# SensorInterface.net
KiCad netlist of a schematic drawn in EAGLE
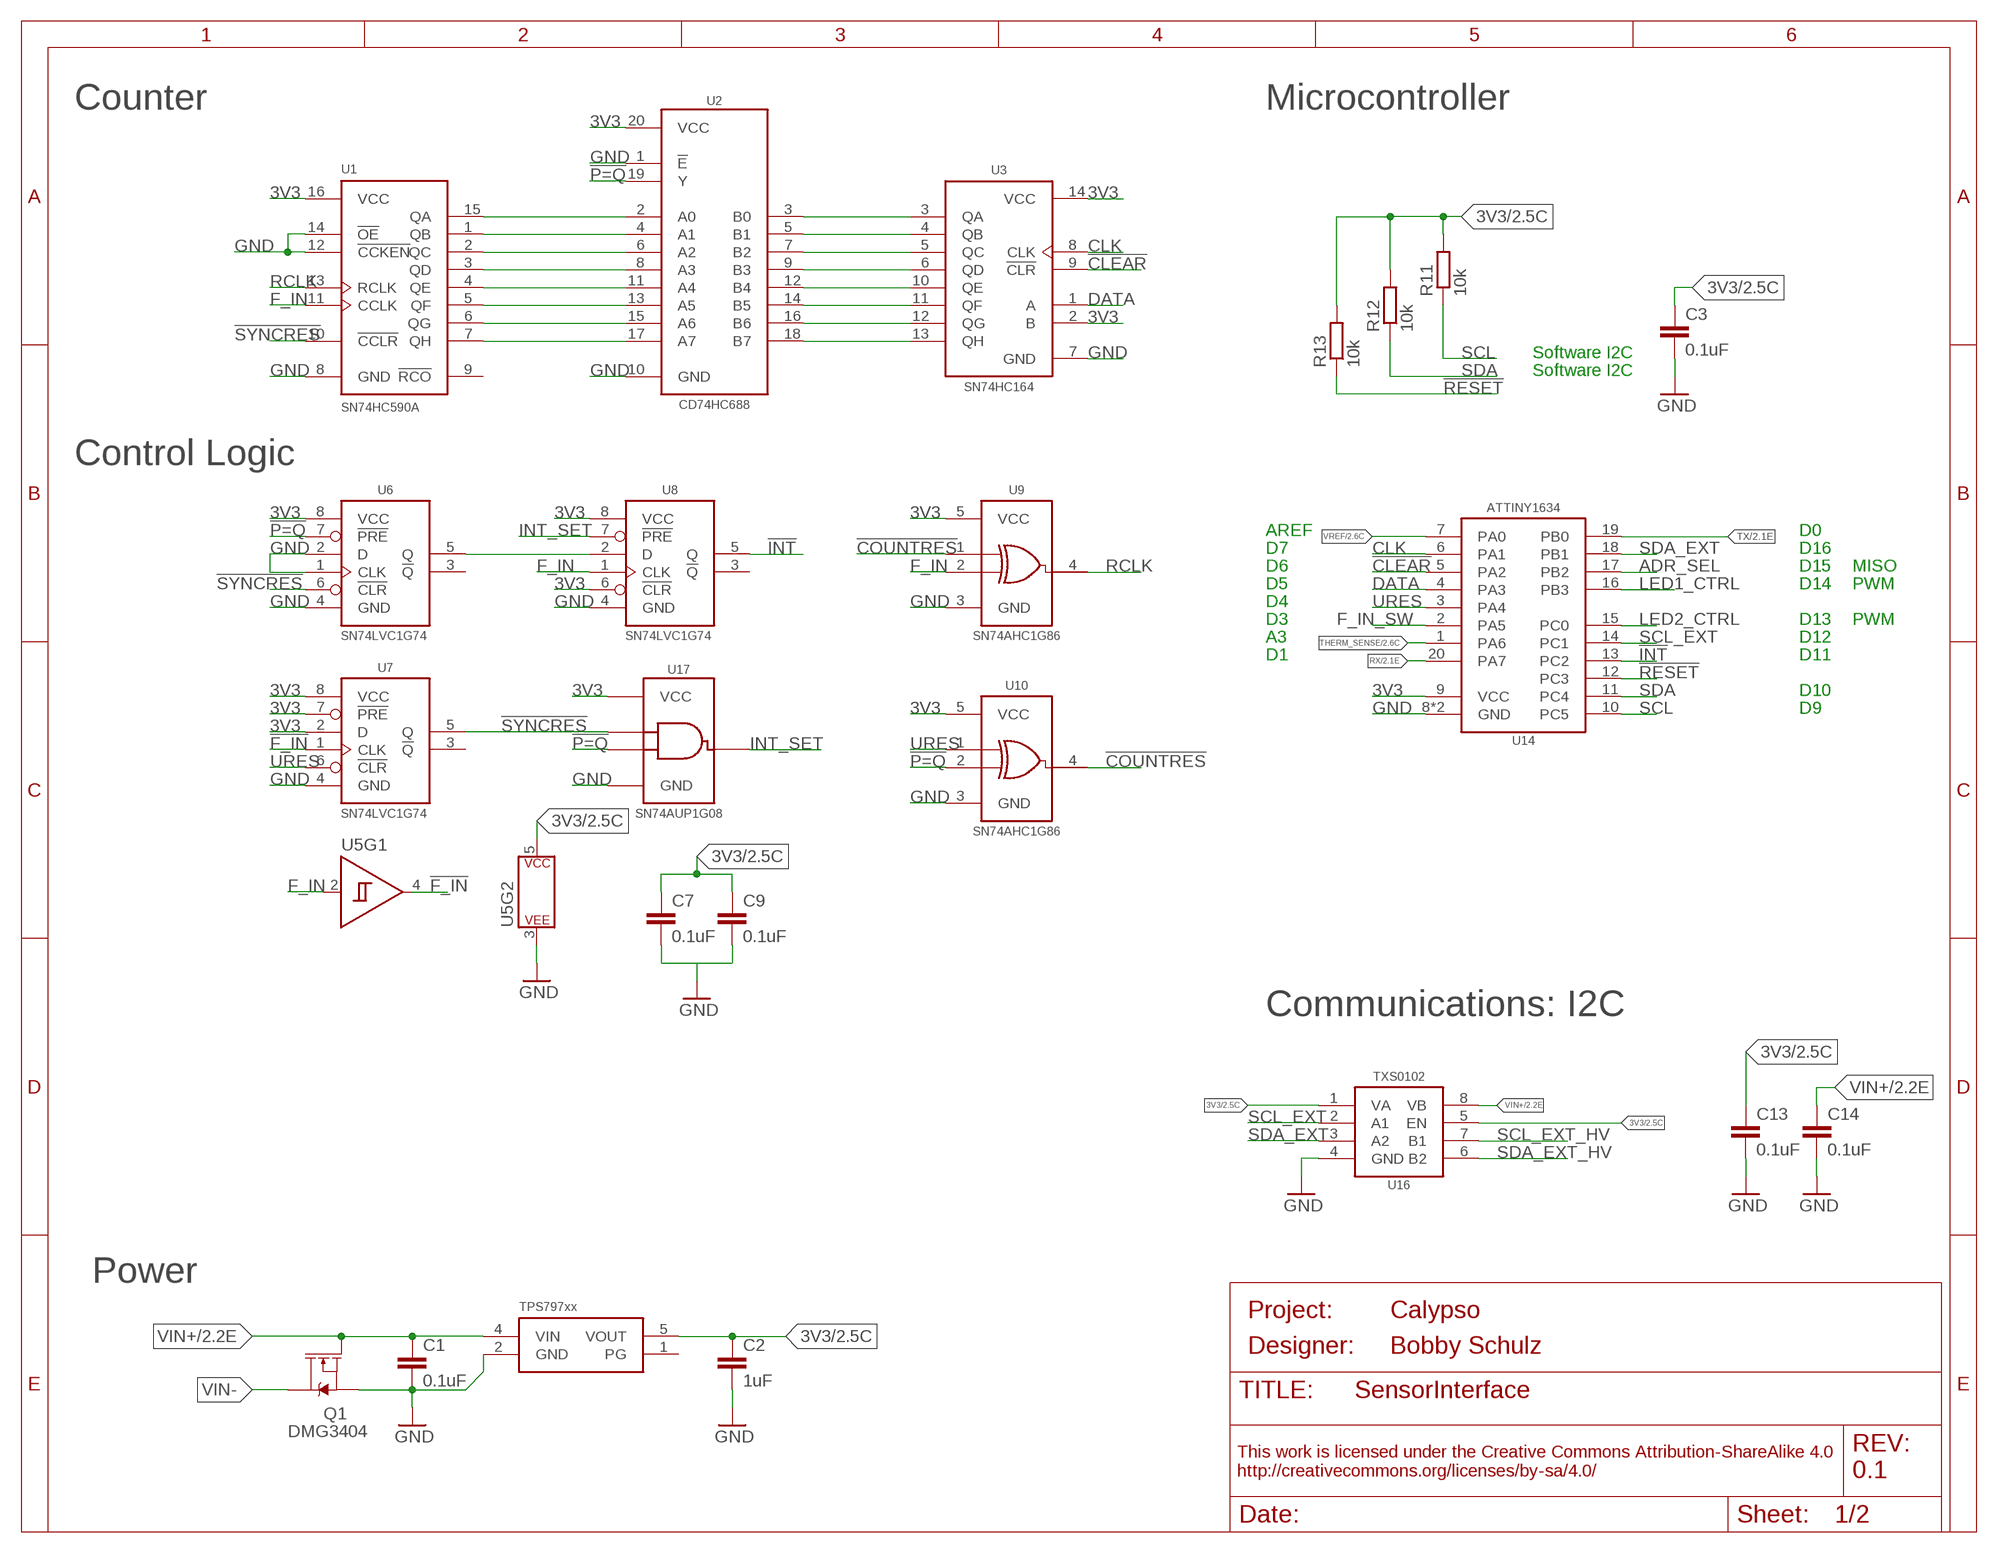
[diagram p0: schematic, sheet 1]
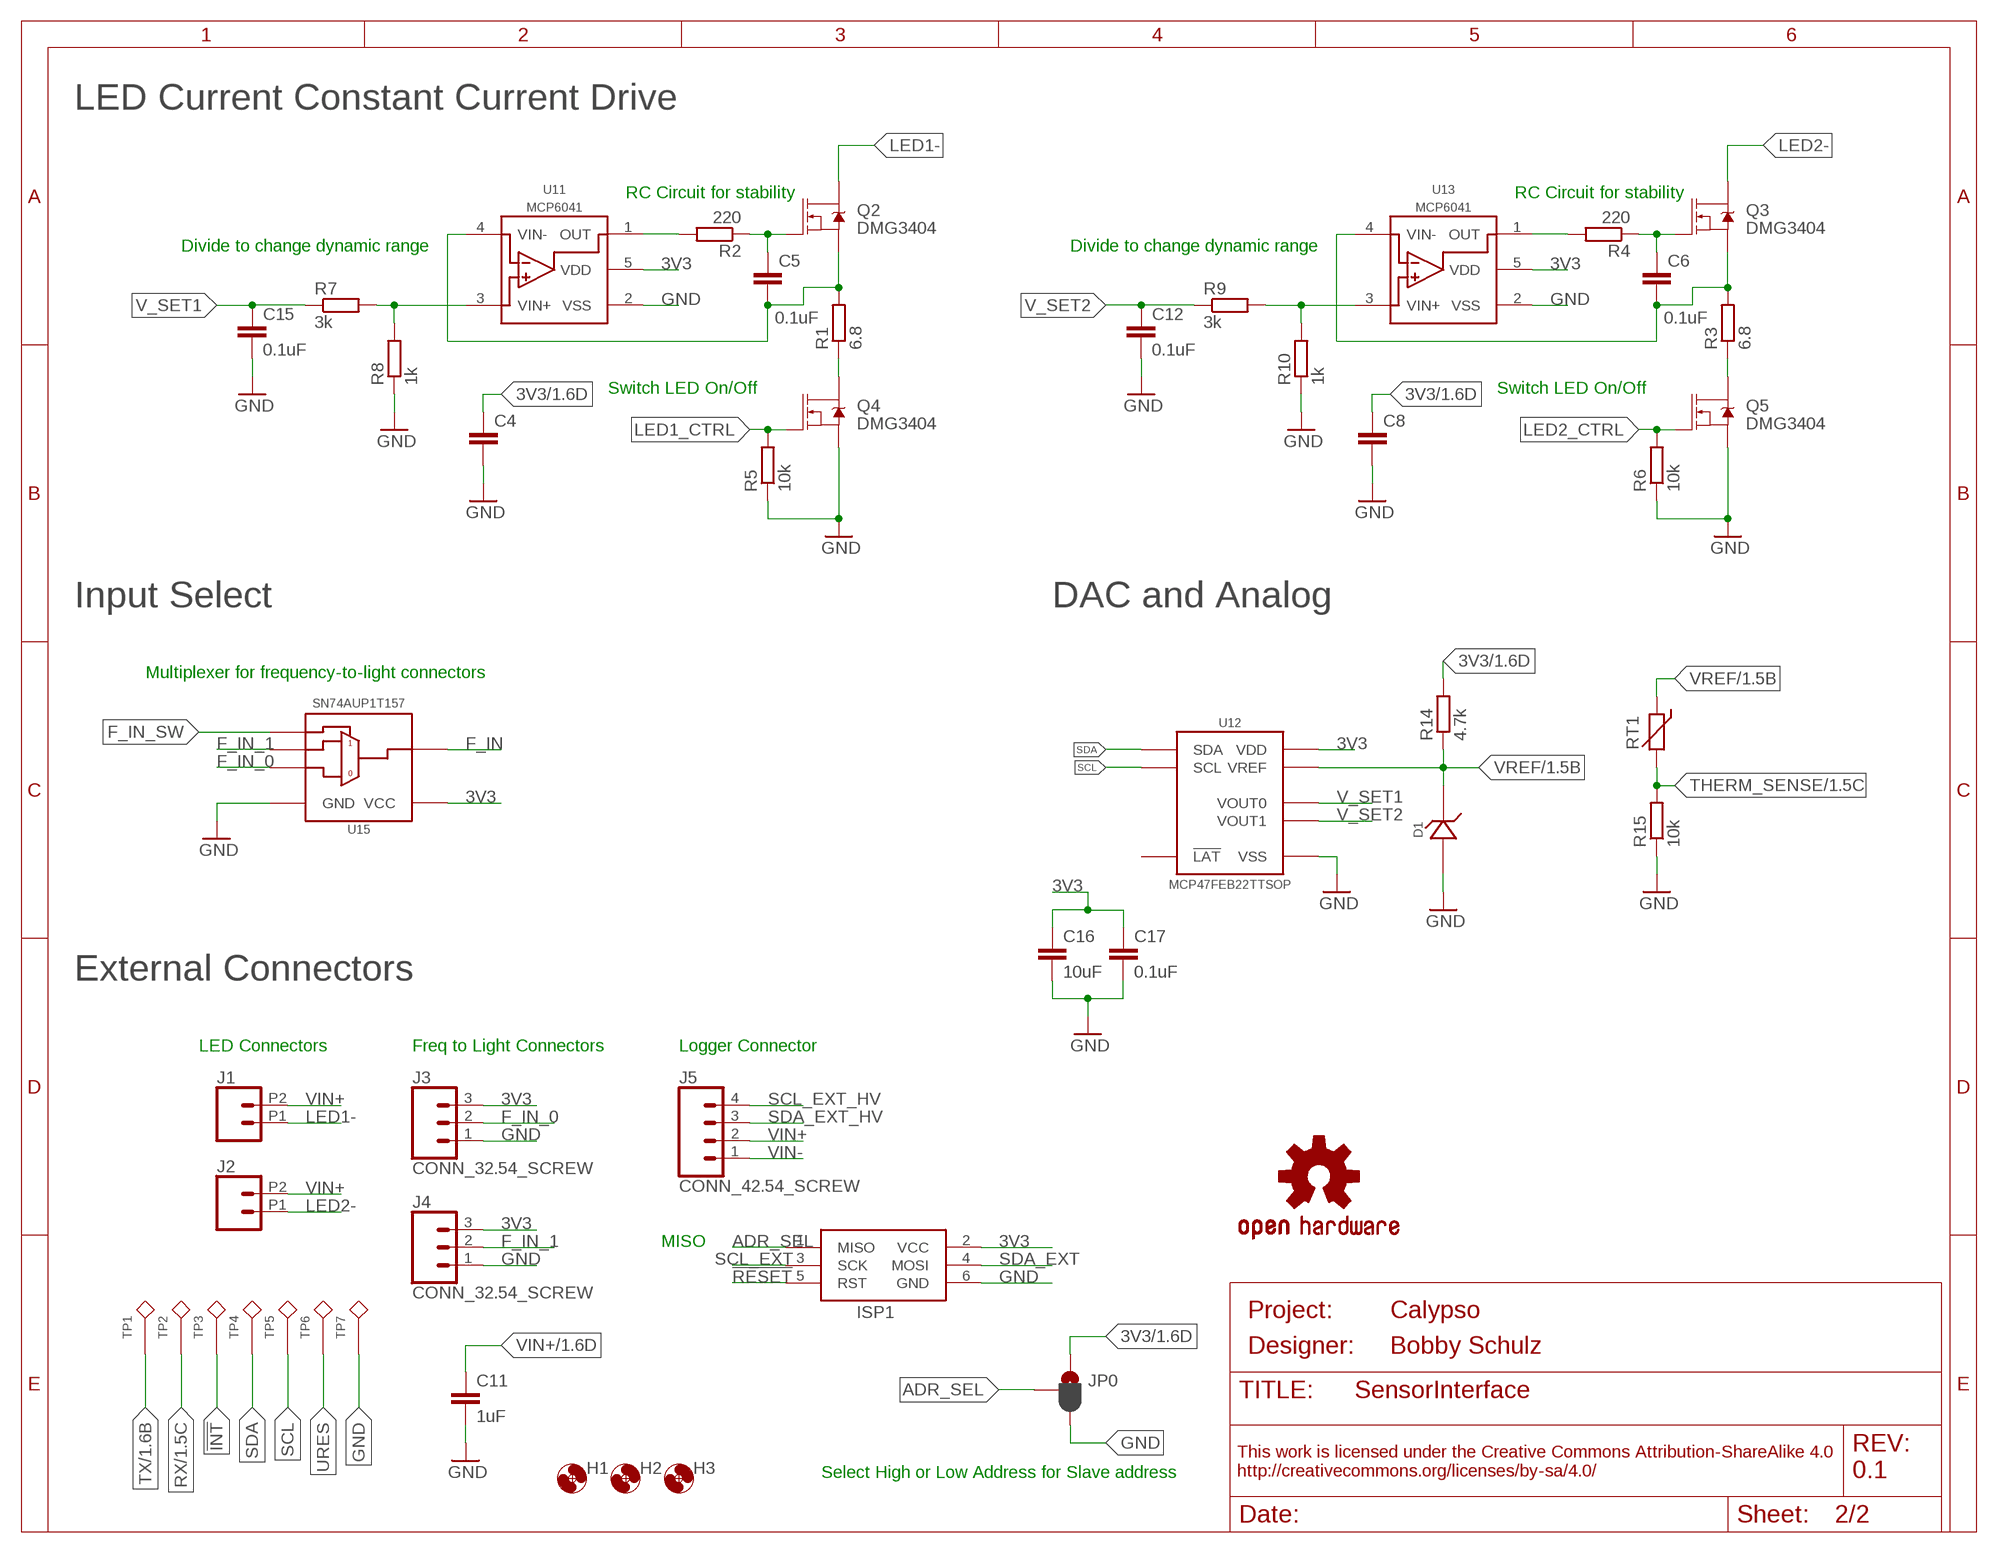
[diagram p1: schematic, sheet 2]

(export (version "E")
  (design (tool "Eeschema 10.0.6"))
  (components
    (comp (ref "C4")
      (value "C-EU0.1UFC0402")
      (footprint "eagle-import:C0402")
      (fields (field (name "MF") "Murata") (field (name "MPN") "GCM155R71C104KA55D"))
      (libsource (lib "eagle-import") (part "C-EUC04020.1UF"))
    )
    (comp (ref "C5")
      (value "0.1uF")
      (footprint "eagle-import:C0603")
      (libsource (lib "eagle-import") (part "C-EUC0603"))
    )
    (comp (ref "C6")
      (value "0.1uF")
      (footprint "eagle-import:C0603")
      (libsource (lib "eagle-import") (part "C-EUC0603"))
    )
    (comp (ref "C8")
      (value "C-EU0.1UFC0402")
      (footprint "eagle-import:C0402")
      (fields (field (name "MF") "Murata") (field (name "MPN") "GCM155R71C104KA55D"))
      (libsource (lib "eagle-import") (part "C-EUC04020.1UF"))
    )
    (comp (ref "C11")
      (value "1uF")
      (footprint "eagle-import:C0603")
      (libsource (lib "eagle-import") (part "C-EUC0603"))
    )
    (comp (ref "C12")
      (value "0.1uF")
      (footprint "eagle-import:C0603")
      (fields (field (name "MF") "Murata") (field (name "MPN") "GCM188R71E104KA57D"))
      (libsource (lib "eagle-import") (part "C-EUC06030.1UF"))
    )
    (comp (ref "C15")
      (value "0.1uF")
      (footprint "eagle-import:C0603")
      (fields (field (name "MF") "Murata") (field (name "MPN") "GCM188R71E104KA57D"))
      (libsource (lib "eagle-import") (part "C-EUC06030.1UF"))
    )
    (comp (ref "C16")
      (value "10uF")
      (footprint "eagle-import:C0805")
      (libsource (lib "eagle-import") (part "C-EUC0805"))
    )
    (comp (ref "C17")
      (value "0.1uF")
      (footprint "eagle-import:C0603")
      (libsource (lib "eagle-import") (part "C-EUC0603"))
    )
    (comp (ref "D1")
      (value "LM40402.048")
      (footprint "eagle-import:SOT23-3")
      (fields (field (name "MF") "TI") (field (name "MPN") "LM4040CIM3-2.0/NOPB"))
      (libsource (lib "eagle-import") (part "LM40402.048"))
    )
    (comp (ref "H1")
      (value "MOUNTING_HOLE2_NP")
      (footprint "eagle-import:2_56")
      (libsource (lib "eagle-import") (part "MOUNTING_HOLE2_NP"))
    )
    (comp (ref "H2")
      (value "MOUNTING_HOLE2_NP")
      (footprint "eagle-import:2_56")
      (libsource (lib "eagle-import") (part "MOUNTING_HOLE2_NP"))
    )
    (comp (ref "H3")
      (value "MOUNTING_HOLE2_NP")
      (footprint "eagle-import:2_56")
      (libsource (lib "eagle-import") (part "MOUNTING_HOLE2_NP"))
    )
    (comp (ref "ISP1")
      (value "AVRISP-6")
      (footprint "eagle-import:AVRISP")
      (libsource (lib "eagle-import") (part "AVRISP-6"))
    )
    (comp (ref "J1")
      (value "CONN_02SCREW_2.54")
      (footprint "eagle-import:1X02_2.54_SCREWTERM")
      (fields (field (name "MF") "OnShore") (field (name "MPN") "OSTVN02A150"))
      (libsource (lib "eagle-import") (part "CONN_02SCREW_2.54"))
    )
    (comp (ref "J2")
      (value "CONN_02SCREW_2.54")
      (footprint "eagle-import:1X02_2.54_SCREWTERM")
      (fields (field (name "MF") "OnShore") (field (name "MPN") "OSTVN02A150"))
      (libsource (lib "eagle-import") (part "CONN_02SCREW_2.54"))
    )
    (comp (ref "J3")
      (value "CONN_32.54_SCREW")
      (footprint "eagle-import:1X03_SCREW")
      (libsource (lib "eagle-import") (part "CONN_32.54_SCREW"))
    )
    (comp (ref "J4")
      (value "CONN_32.54_SCREW")
      (footprint "eagle-import:1X03_SCREW")
      (libsource (lib "eagle-import") (part "CONN_32.54_SCREW"))
    )
    (comp (ref "J5")
      (value "CONN_42.54_SCREW")
      (footprint "eagle-import:1X04_SCREW")
      (fields (field (name "MF") "On Shore") (field (name "MPN") "OSTVN04A150"))
      (libsource (lib "eagle-import") (part "CONN_42.54_SCREW"))
    )
    (comp (ref "JP0")
      (value "JUMPER-SMT_3_1-NC_PASTE_SILK")
      (footprint "eagle-import:SMT-JUMPER_3_1-NC_PASTE_SILK")
      (libsource (lib "eagle-import") (part "JUMPER-SMT_3_1-NC_PASTE_SILK"))
    )
    (comp (ref "LOGO1")
      (value "OSHW-LOGOM")
      (footprint "eagle-import:OSHW-LOGO-M")
      (libsource (lib "eagle-import") (part "OSHW-LOGOM"))
    )
    (comp (ref "Q2")
      (value "DMG3404")
      (footprint "eagle-import:SOT23-3")
      (fields (field (name "MF") "Diodes Incorporated") (field (name "MPN") "DMG3404L-7"))
      (libsource (lib "eagle-import") (part "MOSFET-NCH-DMG3404L"))
    )
    (comp (ref "Q3")
      (value "DMG3404")
      (footprint "eagle-import:SOT23-3")
      (fields (field (name "MF") "Diodes Incorporated") (field (name "MPN") "DMG3404L-7"))
      (libsource (lib "eagle-import") (part "MOSFET-NCH-DMG3404L"))
    )
    (comp (ref "Q4")
      (value "DMG3404")
      (footprint "eagle-import:SOT23-3")
      (fields (field (name "MF") "Diodes Incorporated") (field (name "MPN") "DMG3404L-7"))
      (libsource (lib "eagle-import") (part "MOSFET-NCH-DMG3404L"))
    )
    (comp (ref "Q5")
      (value "DMG3404")
      (footprint "eagle-import:SOT23-3")
      (fields (field (name "MF") "Diodes Incorporated") (field (name "MPN") "DMG3404L-7"))
      (libsource (lib "eagle-import") (part "MOSFET-NCH-DMG3404L"))
    )
    (comp (ref "R1")
      (value "6.8")
      (footprint "eagle-import:R0603")
      (fields (field (name "MF") "Yageo"))
      (libsource (lib "eagle-import") (part "R-EU_R0603"))
    )
    (comp (ref "R2")
      (value "220")
      (footprint "eagle-import:R0603")
      (fields (field (name "MF") "Yageo"))
      (libsource (lib "eagle-import") (part "R-EU_R0603"))
    )
    (comp (ref "R3")
      (value "6.8")
      (footprint "eagle-import:R0603")
      (fields (field (name "MF") "Yageo"))
      (libsource (lib "eagle-import") (part "R-EU_R0603"))
    )
    (comp (ref "R4")
      (value "220")
      (footprint "eagle-import:R0603")
      (fields (field (name "MF") "Yageo"))
      (libsource (lib "eagle-import") (part "R-EU_R0603"))
    )
    (comp (ref "R5")
      (value "10k")
      (footprint "eagle-import:R0603")
      (fields (field (name "MF") "Yageo"))
      (libsource (lib "eagle-import") (part "R-EU_R0603"))
    )
    (comp (ref "R6")
      (value "10k")
      (footprint "eagle-import:R0603")
      (fields (field (name "MF") "Yageo"))
      (libsource (lib "eagle-import") (part "R-EU_R0603"))
    )
    (comp (ref "R7")
      (value "3k")
      (footprint "eagle-import:R0603")
      (fields (field (name "MF") "Yageo"))
      (libsource (lib "eagle-import") (part "R-EU_R0603"))
    )
    (comp (ref "R8")
      (value "1k")
      (footprint "eagle-import:R0603")
      (fields (field (name "MF") "Yageo"))
      (libsource (lib "eagle-import") (part "R-EU_R0603"))
    )
    (comp (ref "R9")
      (value "3k")
      (footprint "eagle-import:R0603")
      (fields (field (name "MF") "Yageo"))
      (libsource (lib "eagle-import") (part "R-EU_R0603"))
    )
    (comp (ref "R10")
      (value "1k")
      (footprint "eagle-import:R0603")
      (fields (field (name "MF") "Yageo"))
      (libsource (lib "eagle-import") (part "R-EU_R0603"))
    )
    (comp (ref "R14")
      (value "4.7k")
      (footprint "eagle-import:R0603")
      (fields (field (name "MF") "Yageo"))
      (libsource (lib "eagle-import") (part "R-EU_R0603"))
    )
    (comp (ref "R15")
      (value "10k")
      (footprint "eagle-import:R0603")
      (fields (field (name "MF") "Panasonic") (field (name "MPN") "ERA-3AEB103V"))
      (libsource (lib "eagle-import") (part "R-EU_R0603P10K"))
    )
    (comp (ref "RT1")
      (value "THERMISTOR10K")
      (footprint "eagle-import:R0603")
      (fields (field (name "MF") "Murata") (field (name "MPN") "NCU18XH103F60RB"))
      (libsource (lib "eagle-import") (part "THERMISTOR10K"))
    )
    (comp (ref "TP1")
      (value "TESTPOINTRCU")
      (footprint "eagle-import:TESTPOINT_0603")
      (fields (field (name "MF") "TE Connectivity") (field (name "MPN") "RCU-0C"))
      (libsource (lib "eagle-import") (part "TESTPOINTRCU"))
    )
    (comp (ref "TP2")
      (value "TESTPOINTRCU")
      (footprint "eagle-import:TESTPOINT_0603")
      (fields (field (name "MF") "TE Connectivity") (field (name "MPN") "RCU-0C"))
      (libsource (lib "eagle-import") (part "TESTPOINTRCU"))
    )
    (comp (ref "TP3")
      (value "TESTPOINTRCU")
      (footprint "eagle-import:TESTPOINT_0603")
      (fields (field (name "MF") "TE Connectivity") (field (name "MPN") "RCU-0C"))
      (libsource (lib "eagle-import") (part "TESTPOINTRCU"))
    )
    (comp (ref "TP4")
      (value "TESTPOINTRCU")
      (footprint "eagle-import:TESTPOINT_0603")
      (fields (field (name "MF") "TE Connectivity") (field (name "MPN") "RCU-0C"))
      (libsource (lib "eagle-import") (part "TESTPOINTRCU"))
    )
    (comp (ref "TP5")
      (value "TESTPOINTRCU")
      (footprint "eagle-import:TESTPOINT_0603")
      (fields (field (name "MF") "TE Connectivity") (field (name "MPN") "RCU-0C"))
      (libsource (lib "eagle-import") (part "TESTPOINTRCU"))
    )
    (comp (ref "TP6")
      (value "TESTPOINTRCU")
      (footprint "eagle-import:TESTPOINT_0603")
      (fields (field (name "MF") "TE Connectivity") (field (name "MPN") "RCU-0C"))
      (libsource (lib "eagle-import") (part "TESTPOINTRCU"))
    )
    (comp (ref "TP7")
      (value "TESTPOINTRCU")
      (footprint "eagle-import:TESTPOINT_0603")
      (fields (field (name "MF") "TE Connectivity") (field (name "MPN") "RCU-0C"))
      (libsource (lib "eagle-import") (part "TESTPOINTRCU"))
    )
    (comp (ref "U11")
      (value "MCP6041")
      (footprint "eagle-import:SOT23-5")
      (fields
        (field (name "DISP") "MCP6041")
        (field (name "MF") "Microchip")
        (field (name "MPN") "MCP6041T-I/OT")
      )
      (libsource (lib "eagle-import") (part "MCP6041"))
    )
    (comp (ref "U12")
      (value "MCP47FEB22TTSOP")
      (footprint "eagle-import:TTSOP_8")
      (fields (field (name "MF") "Microchip") (field (name "MPN") "MCP47FEB22A0-E/ST"))
      (libsource (lib "eagle-import") (part "MCP47FEB2TTSOP2"))
    )
    (comp (ref "U13")
      (value "MCP6041")
      (footprint "eagle-import:SOT23-5")
      (fields
        (field (name "DISP") "MCP6041")
        (field (name "MF") "Microchip")
        (field (name "MPN") "MCP6041T-I/OT")
      )
      (libsource (lib "eagle-import") (part "MCP6041"))
    )
    (comp (ref "U15")
      (value "SN74AUP1T157DCK")
      (footprint "eagle-import:DCK_R-PDSO-G6")
      (fields
        (field (name "DISP") "SN74AUP1T157")
        (field (name "MF") "TI")
        (field (name "MPN") "SN74AUP1T157DCKR")
      )
      (libsource (lib "eagle-import") (part "SN74AUP1T157DCK"))
    )
    (comp (ref "C1")
      (value "0.1uF")
      (footprint "eagle-import:C0603")
      (fields (field (name "MF") "Murata") (field (name "MPN") "GCM188R71E104KA57D"))
      (libsource (lib "eagle-import") (part "C-EUC06030.1UF"))
    )
    (comp (ref "C2")
      (value "1uF")
      (footprint "eagle-import:C0603")
      (fields (field (name "MF") "Murata") (field (name "MPN") "GRM188R61C105KA12D"))
      (libsource (lib "eagle-import") (part "C-EUC06031UF"))
    )
    (comp (ref "C3")
      (value "0.1uF")
      (footprint "eagle-import:C0402")
      (fields (field (name "MF") "Murata") (field (name "MPN") "GCM155R71C104KA55D"))
      (libsource (lib "eagle-import") (part "C-EUC04020.1UF"))
    )
    (comp (ref "C7")
      (value "0.1uF")
      (footprint "eagle-import:C0603")
      (libsource (lib "eagle-import") (part "C-EUC0603"))
    )
    (comp (ref "C9")
      (value "0.1uF")
      (footprint "eagle-import:C0603")
      (libsource (lib "eagle-import") (part "C-EUC0603"))
    )
    (comp (ref "C13")
      (value "0.1uF")
      (footprint "eagle-import:C0402")
      (fields (field (name "MF") "Murata") (field (name "MPN") "GCM155R71C104KA55D"))
      (libsource (lib "eagle-import") (part "C-EUC04020.1UF"))
    )
    (comp (ref "C14")
      (value "0.1uF")
      (footprint "eagle-import:C0402")
      (fields (field (name "MF") "Murata") (field (name "MPN") "GCM155R71C104KA55D"))
      (libsource (lib "eagle-import") (part "C-EUC04020.1UF"))
    )
    (comp (ref "Q1")
      (value "DMG3404")
      (footprint "eagle-import:SOT23-3")
      (fields (field (name "MF") "Diodes Incorporated") (field (name "MPN") "DMG3404L-7"))
      (libsource (lib "eagle-import") (part "MOSFET-NCH-DMG3404L"))
    )
    (comp (ref "R11")
      (value "10k")
      (footprint "eagle-import:R0402")
      (fields (field (name "MF") "Yageo") (field (name "MPN") "RC0402JR-0710KL"))
      (libsource (lib "eagle-import") (part "R-EU_R040210K"))
    )
    (comp (ref "R12")
      (value "10k")
      (footprint "eagle-import:R0402")
      (fields (field (name "MF") "Yageo") (field (name "MPN") "RC0402JR-0710KL"))
      (libsource (lib "eagle-import") (part "R-EU_R040210K"))
    )
    (comp (ref "R13")
      (value "10k")
      (footprint "eagle-import:R0402")
      (fields (field (name "MF") "Yageo") (field (name "MPN") "RC0402JR-0710KL"))
      (libsource (lib "eagle-import") (part "R-EU_R040210K"))
    )
    (comp (ref "U$1")
      (value "TPS79733")
      (footprint "eagle-import:DCK_R-PDSO-G5")
      (fields (field (name "MF") "TI") (field (name "MPN") "TPS79733DCKR"))
      (libsource (lib "eagle-import") (part "TPS79733"))
    )
    (comp (ref "U1")
      (value "SN74HC590AD")
      (footprint "eagle-import:SO16")
      (fields (field (name "MF") "TI"))
      (libsource (lib "eagle-import") (part "SN74HC590AD"))
    )
    (comp (ref "U2")
      (value "CD74HCT688DW")
      (footprint "eagle-import:SO-20DW")
      (libsource (lib "eagle-import") (part "CD74HCT688DW"))
    )
    (comp (ref "U3")
      (value "SN74HC164D")
      (footprint "eagle-import:SO14")
      (fields (field (name "MF") "TI") (field (name "MPN") "SN74HC164DR"))
      (libsource (lib "eagle-import") (part "SN74HC164D"))
    )
    (comp (ref "U5")
      (value "SN74LVC1G14DCK")
      (footprint "eagle-import:DCK_R-PDSO-G5")
      (fields (field (name "MF") "TI") (field (name "MPN") "SN74LVC1G14DCKR"))
      (libsource (lib "eagle-import") (part "SN741G14DCKLVC"))
    )
    (comp (ref "U6")
      (value "SN74LVC1G74DCU")
      (footprint "eagle-import:DCU_(R-PDSO-G8)")
      (fields (field (name "MF") "TI") (field (name "MPN") "SN74LVC1G74DCUR"))
      (libsource (lib "eagle-import") (part "SN74LVC1G74DCU"))
    )
    (comp (ref "U7")
      (value "SN74LVC1G74DCU")
      (footprint "eagle-import:DCU_(R-PDSO-G8)")
      (fields (field (name "MF") "TI") (field (name "MPN") "SN74LVC1G74DCUR"))
      (libsource (lib "eagle-import") (part "SN74LVC1G74DCU"))
    )
    (comp (ref "U8")
      (value "SN74LVC1G74DCU")
      (footprint "eagle-import:DCU_(R-PDSO-G8)")
      (fields (field (name "MF") "TI") (field (name "MPN") "SN74LVC1G74DCUR"))
      (libsource (lib "eagle-import") (part "SN74LVC1G74DCU"))
    )
    (comp (ref "U9")
      (value "SN74AHC1G86DCK")
      (footprint "eagle-import:DCK_R-PDSO-G5")
      (fields (field (name "MF") "TI") (field (name "MPN") "SN74AHC1G86DCKR"))
      (libsource (lib "eagle-import") (part "SN74AHC1G86DCK"))
    )
    (comp (ref "U10")
      (value "SN74AHC1G86DCK")
      (footprint "eagle-import:DCK_R-PDSO-G5")
      (fields (field (name "MF") "TI") (field (name "MPN") "SN74AHC1G86DCKR"))
      (libsource (lib "eagle-import") (part "SN74AHC1G86DCK"))
    )
    (comp (ref "U14")
      (value "ATTINY1634QFN")
      (footprint "eagle-import:QFN20")
      (fields (field (name "MF") "Atmel") (field (name "MPN") "ATTINY1634-MUR"))
      (libsource (lib "eagle-import") (part "ATTINY1634QFN"))
    )
    (comp (ref "U16")
      (value "TXS0102DQM")
      (footprint "eagle-import:DQM_R-PX2SON-N8")
      (fields (field (name "MF") "TI") (field (name "MPN") "TXS0102DQMR"))
      (libsource (lib "eagle-import") (part "TXS0102DQM"))
    )
    (comp (ref "U17")
      (value "SN74AUP1G08DCK")
      (footprint "eagle-import:DCK_R-PDSO-G5")
      (fields (field (name "MF") "TI") (field (name "MPN") "SN74AUP1G08DCKR"))
      (libsource (lib "eagle-import") (part "SN74AUP1G08DCK"))
    )
  )
  (nets
    (net (code "1") (name "3V3") (class "Default")
      (node (ref "C13") (pin "1") (pinfunction "1_1") (pintype "passive"))
      (node (ref "C16") (pin "1") (pinfunction "1_1") (pintype "passive"))
      (node (ref "C17") (pin "1") (pinfunction "1_1") (pintype "passive"))
      (node (ref "C2") (pin "1") (pinfunction "1_1") (pintype "passive"))
      (node (ref "C3") (pin "1") (pinfunction "1_1") (pintype "passive"))
      (node (ref "C4") (pin "1") (pinfunction "1_1") (pintype "passive"))
      (node (ref "C7") (pin "1") (pinfunction "1_1") (pintype "passive"))
      (node (ref "C8") (pin "1") (pinfunction "1_1") (pintype "passive"))
      (node (ref "C9") (pin "1") (pinfunction "1_1") (pintype "passive"))
      (node (ref "ISP1") (pin "2") (pinfunction "VCC_2") (pintype "power_in"))
      (node (ref "J3") (pin "3") (pinfunction "3_3") (pintype "passive"))
      (node (ref "J4") (pin "3") (pinfunction "3_3") (pintype "passive"))
      (node (ref "JP0") (pin "1") (pinfunction "1_1") (pintype "passive"))
      (node (ref "R11") (pin "2") (pinfunction "2_2") (pintype "passive"))
      (node (ref "R12") (pin "2") (pinfunction "2_2") (pintype "passive"))
      (node (ref "R13") (pin "2") (pinfunction "2_2") (pintype "passive"))
      (node (ref "R14") (pin "2") (pinfunction "2_2") (pintype "passive"))
      (node (ref "U$1") (pin "5") (pinfunction "VOUT_5") (pintype "bidirectional"))
      (node (ref "U1") (pin "16") (pinfunction "VCC_16") (pintype "power_in"))
      (node (ref "U10") (pin "5") (pinfunction "VCC_5") (pintype "power_in"))
      (node (ref "U11") (pin "5") (pinfunction "VDD_5") (pintype "power_in"))
      (node (ref "U12") (pin "1") (pinfunction "VDD_1") (pintype "power_in"))
      (node (ref "U13") (pin "5") (pinfunction "VDD_5") (pintype "power_in"))
      (node (ref "U14") (pin "9") (pinfunction "VCC_9") (pintype "power_in"))
      (node (ref "U15") (pin "5") (pinfunction "VCC_5") (pintype "power_in"))
      (node (ref "U16") (pin "1") (pinfunction "VA_1") (pintype "power_in"))
      (node (ref "U16") (pin "5") (pinfunction "EN_5") (pintype "input"))
      (node (ref "U17") (pin "5") (pinfunction "VCC_5") (pintype "power_in"))
      (node (ref "U2") (pin "20") (pinfunction "VCC_20") (pintype "power_in"))
      (node (ref "U3") (pin "14") (pinfunction "VCC_14") (pintype "power_in"))
      (node (ref "U3") (pin "2") (pinfunction "B_2") (pintype "input"))
      (node (ref "U5") (pin "5") (pinfunction "P$V+_5") (pintype "bidirectional"))
      (node (ref "U6") (pin "8") (pinfunction "VCC_8") (pintype "output"))
      (node (ref "U7") (pin "2") (pinfunction "D_2") (pintype "output"))
      (node (ref "U7") (pin "7") (pinfunction "~{PRE}_7") (pintype "output"))
      (node (ref "U7") (pin "8") (pinfunction "VCC_8") (pintype "output"))
      (node (ref "U8") (pin "6") (pinfunction "~{CLR}_6") (pintype "output"))
      (node (ref "U8") (pin "8") (pinfunction "VCC_8") (pintype "output"))
      (node (ref "U9") (pin "5") (pinfunction "VCC_5") (pintype "power_in"))
    )
    (net (code "2") (name "ADR_SEL") (class "Default")
      (node (ref "ISP1") (pin "1") (pinfunction "MISO_1") (pintype "input"))
      (node (ref "JP0") (pin "2") (pinfunction "2_2") (pintype "passive"))
      (node (ref "U14") (pin "17") (pinfunction "PB2_17") (pintype "bidirectional"))
    )
    (net (code "3") (name "CLK") (class "Default")
      (node (ref "U14") (pin "6") (pinfunction "PA1_6") (pintype "bidirectional"))
      (node (ref "U3") (pin "8") (pinfunction "CLK_8") (pintype "input"))
    )
    (net (code "4") (name "DATA") (class "Default")
      (node (ref "U14") (pin "4") (pinfunction "PA3_4") (pintype "bidirectional"))
      (node (ref "U3") (pin "1") (pinfunction "A_1") (pintype "input"))
    )
    (net (code "5") (name "F_IN") (class "Default")
      (node (ref "U1") (pin "11") (pinfunction "CCLK_11") (pintype "input"))
      (node (ref "U15") (pin "6") (pinfunction "Y_6") (pintype "output"))
      (node (ref "U5") (pin "2") (pinfunction "A_2") (pintype "bidirectional"))
      (node (ref "U8") (pin "1") (pinfunction "CLK_1") (pintype "output"))
      (node (ref "U9") (pin "2") (pinfunction "B_2") (pintype "input"))
    )
    (net (code "6") (name "F_IN_0") (class "Default")
      (node (ref "J3") (pin "2") (pinfunction "2_2") (pintype "passive"))
      (node (ref "U15") (pin "3") (pinfunction "B_3") (pintype "input"))
    )
    (net (code "7") (name "F_IN_1") (class "Default")
      (node (ref "J4") (pin "2") (pinfunction "2_2") (pintype "passive"))
      (node (ref "U15") (pin "1") (pinfunction "A_1") (pintype "input"))
    )
    (net (code "8") (name "F_IN_SW") (class "Default")
      (node (ref "U14") (pin "2") (pinfunction "PA5_2") (pintype "bidirectional"))
      (node (ref "U15") (pin "4") (pinfunction "C_4") (pintype "input"))
    )
    (net (code "9") (name "GND") (class "Default")
      (node (ref "C1") (pin "2") (pinfunction "2_2") (pintype "passive"))
      (node (ref "C11") (pin "2") (pinfunction "2_2") (pintype "passive"))
      (node (ref "C12") (pin "2") (pinfunction "2_2") (pintype "passive"))
      (node (ref "C13") (pin "2") (pinfunction "2_2") (pintype "passive"))
      (node (ref "C14") (pin "2") (pinfunction "2_2") (pintype "passive"))
      (node (ref "C15") (pin "2") (pinfunction "2_2") (pintype "passive"))
      (node (ref "C16") (pin "2") (pinfunction "2_2") (pintype "passive"))
      (node (ref "C17") (pin "2") (pinfunction "2_2") (pintype "passive"))
      (node (ref "C2") (pin "2") (pinfunction "2_2") (pintype "passive"))
      (node (ref "C3") (pin "2") (pinfunction "2_2") (pintype "passive"))
      (node (ref "C4") (pin "2") (pinfunction "2_2") (pintype "passive"))
      (node (ref "C7") (pin "2") (pinfunction "2_2") (pintype "passive"))
      (node (ref "C8") (pin "2") (pinfunction "2_2") (pintype "passive"))
      (node (ref "C9") (pin "2") (pinfunction "2_2") (pintype "passive"))
      (node (ref "D1") (pin "2") (pinfunction "A_2") (pintype "power_in"))
      (node (ref "ISP1") (pin "6") (pinfunction "GND_6") (pintype "power_in"))
      (node (ref "J3") (pin "1") (pinfunction "1_1") (pintype "passive"))
      (node (ref "J4") (pin "1") (pinfunction "1_1") (pintype "passive"))
      (node (ref "JP0") (pin "3") (pinfunction "3_3") (pintype "passive"))
      (node (ref "Q1") (pin "2") (pinfunction "S_2") (pintype "bidirectional"))
      (node (ref "Q4") (pin "2") (pinfunction "S_2") (pintype "bidirectional"))
      (node (ref "Q5") (pin "2") (pinfunction "S_2") (pintype "bidirectional"))
      (node (ref "R10") (pin "1") (pinfunction "1_1") (pintype "passive"))
      (node (ref "R15") (pin "1") (pinfunction "1_1") (pintype "passive"))
      (node (ref "R5") (pin "1") (pinfunction "1_1") (pintype "passive"))
      (node (ref "R6") (pin "1") (pinfunction "1_1") (pintype "passive"))
      (node (ref "R8") (pin "1") (pinfunction "1_1") (pintype "passive"))
      (node (ref "TP7") (pin "1") (pinfunction "P$1_1") (pintype "bidirectional"))
      (node (ref "U$1") (pin "2") (pinfunction "GND_2") (pintype "bidirectional"))
      (node (ref "U1") (pin "12") (pinfunction "~{CCKEN}_12") (pintype "input"))
      (node (ref "U1") (pin "14") (pinfunction "~{OE}_14") (pintype "input"))
      (node (ref "U1") (pin "8") (pinfunction "GND_8") (pintype "power_in"))
      (node (ref "U10") (pin "3") (pinfunction "GND_3") (pintype "power_in"))
      (node (ref "U11") (pin "2") (pinfunction "VSS_2") (pintype "power_in"))
      (node (ref "U12") (pin "5") (pinfunction "VSS_5") (pintype "power_in"))
      (node (ref "U13") (pin "2") (pinfunction "VSS_2") (pintype "power_in"))
      (node (ref "U14") (pin "8") (pinfunction "GND_8") (pintype "power_in"))
      (node (ref "U14") (pin "EP") (pinfunction "GND_EP") (pintype "power_in"))
      (node (ref "U15") (pin "2") (pinfunction "GND_2") (pintype "power_in"))
      (node (ref "U16") (pin "4") (pinfunction "GND_4") (pintype "power_in"))
      (node (ref "U17") (pin "3") (pinfunction "GND_3") (pintype "power_in"))
      (node (ref "U2") (pin "1") (pinfunction "~{E}_1") (pintype "input"))
      (node (ref "U2") (pin "10") (pinfunction "GND_10") (pintype "power_in"))
      (node (ref "U3") (pin "7") (pinfunction "GND_7") (pintype "power_in"))
      (node (ref "U5") (pin "3") (pinfunction "P$V-_3") (pintype "bidirectional"))
      (node (ref "U6") (pin "1") (pinfunction "CLK_1") (pintype "output"))
      (node (ref "U6") (pin "2") (pinfunction "D_2") (pintype "output"))
      (node (ref "U6") (pin "4") (pinfunction "GND_4") (pintype "output"))
      (node (ref "U7") (pin "4") (pinfunction "GND_4") (pintype "output"))
      (node (ref "U8") (pin "4") (pinfunction "GND_4") (pintype "output"))
      (node (ref "U9") (pin "3") (pinfunction "GND_3") (pintype "power_in"))
    )
    (net (code "10") (name "INT_SET") (class "Default")
      (node (ref "U17") (pin "4") (pinfunction "Y_4") (pintype "output"))
      (node (ref "U8") (pin "7") (pinfunction "~{PRE}_7") (pintype "output"))
    )
    (net (code "11") (name "LED1-") (class "Default")
      (node (ref "J1") (pin "P1") (pinfunction "1_P1") (pintype "passive"))
      (node (ref "Q2") (pin "3") (pinfunction "D_3") (pintype "bidirectional"))
    )
    (net (code "12") (name "LED1_CTRL") (class "Default")
      (node (ref "Q4") (pin "1") (pinfunction "G_1") (pintype "bidirectional"))
      (node (ref "R5") (pin "2") (pinfunction "2_2") (pintype "passive"))
      (node (ref "U14") (pin "16") (pinfunction "PB3_16") (pintype "bidirectional"))
    )
    (net (code "13") (name "LED2-") (class "Default")
      (node (ref "J2") (pin "P1") (pinfunction "1_P1") (pintype "passive"))
      (node (ref "Q3") (pin "3") (pinfunction "D_3") (pintype "bidirectional"))
    )
    (net (code "14") (name "LED2_CTRL") (class "Default")
      (node (ref "Q5") (pin "1") (pinfunction "G_1") (pintype "bidirectional"))
      (node (ref "R6") (pin "2") (pinfunction "2_2") (pintype "passive"))
      (node (ref "U14") (pin "15") (pinfunction "PC0_15") (pintype "bidirectional"))
    )
    (net (code "15") (name "Net-(Q2-G)") (class "Default")
      (node (ref "C5") (pin "1") (pinfunction "1_1") (pintype "passive"))
      (node (ref "Q2") (pin "1") (pinfunction "G_1") (pintype "bidirectional"))
      (node (ref "R2") (pin "1") (pinfunction "1_1") (pintype "passive"))
    )
    (net (code "16") (name "Net-(Q2-S)") (class "Default")
      (node (ref "C5") (pin "2") (pinfunction "2_2") (pintype "passive"))
      (node (ref "Q2") (pin "2") (pinfunction "S_2") (pintype "bidirectional"))
      (node (ref "R1") (pin "2") (pinfunction "2_2") (pintype "passive"))
      (node (ref "U11") (pin "4") (pinfunction "VIN-_4") (pintype "input"))
    )
    (net (code "17") (name "Net-(Q3-G)") (class "Default")
      (node (ref "C6") (pin "1") (pinfunction "1_1") (pintype "passive"))
      (node (ref "Q3") (pin "1") (pinfunction "G_1") (pintype "bidirectional"))
      (node (ref "R4") (pin "1") (pinfunction "1_1") (pintype "passive"))
    )
    (net (code "18") (name "Net-(Q3-S)") (class "Default")
      (node (ref "C6") (pin "2") (pinfunction "2_2") (pintype "passive"))
      (node (ref "Q3") (pin "2") (pinfunction "S_2") (pintype "bidirectional"))
      (node (ref "R3") (pin "2") (pinfunction "2_2") (pintype "passive"))
      (node (ref "U13") (pin "4") (pinfunction "VIN-_4") (pintype "input"))
    )
    (net (code "19") (name "Net-(Q4-D)") (class "Default")
      (node (ref "Q4") (pin "3") (pinfunction "D_3") (pintype "bidirectional"))
      (node (ref "R1") (pin "1") (pinfunction "1_1") (pintype "passive"))
    )
    (net (code "20") (name "Net-(Q5-D)") (class "Default")
      (node (ref "Q5") (pin "3") (pinfunction "D_3") (pintype "bidirectional"))
      (node (ref "R3") (pin "1") (pinfunction "1_1") (pintype "passive"))
    )
    (net (code "21") (name "Net-(U1-QA)") (class "Default")
      (node (ref "U1") (pin "15") (pinfunction "QA_15") (pintype "output"))
      (node (ref "U2") (pin "2") (pinfunction "A0_2") (pintype "input"))
    )
    (net (code "22") (name "Net-(U1-QB)") (class "Default")
      (node (ref "U1") (pin "1") (pinfunction "QB_1") (pintype "output"))
      (node (ref "U2") (pin "4") (pinfunction "A1_4") (pintype "input"))
    )
    (net (code "23") (name "Net-(U1-QC)") (class "Default")
      (node (ref "U1") (pin "2") (pinfunction "QC_2") (pintype "output"))
      (node (ref "U2") (pin "6") (pinfunction "A2_6") (pintype "input"))
    )
    (net (code "24") (name "Net-(U1-QD)") (class "Default")
      (node (ref "U1") (pin "3") (pinfunction "QD_3") (pintype "output"))
      (node (ref "U2") (pin "8") (pinfunction "A3_8") (pintype "input"))
    )
    (net (code "25") (name "Net-(U1-QE)") (class "Default")
      (node (ref "U1") (pin "4") (pinfunction "QE_4") (pintype "output"))
      (node (ref "U2") (pin "11") (pinfunction "A4_11") (pintype "input"))
    )
    (net (code "26") (name "Net-(U1-QF)") (class "Default")
      (node (ref "U1") (pin "5") (pinfunction "QF_5") (pintype "output"))
      (node (ref "U2") (pin "13") (pinfunction "A5_13") (pintype "input"))
    )
    (net (code "27") (name "Net-(U1-QG)") (class "Default")
      (node (ref "U1") (pin "6") (pinfunction "QG_6") (pintype "output"))
      (node (ref "U2") (pin "15") (pinfunction "A6_15") (pintype "input"))
    )
    (net (code "28") (name "Net-(U1-QH)") (class "Default")
      (node (ref "U1") (pin "7") (pinfunction "QH_7") (pintype "output"))
      (node (ref "U2") (pin "17") (pinfunction "A7_17") (pintype "input"))
    )
    (net (code "29") (name "Net-(U2-B0)") (class "Default")
      (node (ref "U2") (pin "3") (pinfunction "B0_3") (pintype "input"))
      (node (ref "U3") (pin "3") (pinfunction "QA_3") (pintype "output"))
    )
    (net (code "30") (name "Net-(U2-B1)") (class "Default")
      (node (ref "U2") (pin "5") (pinfunction "B1_5") (pintype "input"))
      (node (ref "U3") (pin "4") (pinfunction "QB_4") (pintype "output"))
    )
    (net (code "31") (name "Net-(U2-B2)") (class "Default")
      (node (ref "U2") (pin "7") (pinfunction "B2_7") (pintype "input"))
      (node (ref "U3") (pin "5") (pinfunction "QC_5") (pintype "output"))
    )
    (net (code "32") (name "Net-(U2-B3)") (class "Default")
      (node (ref "U2") (pin "9") (pinfunction "B3_9") (pintype "input"))
      (node (ref "U3") (pin "6") (pinfunction "QD_6") (pintype "output"))
    )
    (net (code "33") (name "Net-(U2-B4)") (class "Default")
      (node (ref "U2") (pin "12") (pinfunction "B4_12") (pintype "input"))
      (node (ref "U3") (pin "10") (pinfunction "QE_10") (pintype "output"))
    )
    (net (code "34") (name "Net-(U2-B5)") (class "Default")
      (node (ref "U2") (pin "14") (pinfunction "B5_14") (pintype "input"))
      (node (ref "U3") (pin "11") (pinfunction "QF_11") (pintype "output"))
    )
    (net (code "35") (name "Net-(U2-B6)") (class "Default")
      (node (ref "U2") (pin "16") (pinfunction "B6_16") (pintype "input"))
      (node (ref "U3") (pin "12") (pinfunction "QG_12") (pintype "output"))
    )
    (net (code "36") (name "Net-(U2-B7)") (class "Default")
      (node (ref "U2") (pin "18") (pinfunction "B7_18") (pintype "input"))
      (node (ref "U3") (pin "13") (pinfunction "QH_13") (pintype "output"))
    )
    (net (code "37") (name "Net-(U6-Q)") (class "Default")
      (node (ref "U6") (pin "5") (pinfunction "Q_5") (pintype "output"))
      (node (ref "U8") (pin "2") (pinfunction "D_2") (pintype "output"))
    )
    (net (code "38") (name "Net-(U11-OUT)") (class "Default")
      (node (ref "R2") (pin "2") (pinfunction "2_2") (pintype "passive"))
      (node (ref "U11") (pin "1") (pinfunction "OUT_1") (pintype "output"))
    )
    (net (code "39") (name "Net-(U11-VIN+)") (class "Default")
      (node (ref "R7") (pin "2") (pinfunction "2_2") (pintype "passive"))
      (node (ref "R8") (pin "2") (pinfunction "2_2") (pintype "passive"))
      (node (ref "U11") (pin "3") (pinfunction "VIN+_3") (pintype "input"))
    )
    (net (code "40") (name "Net-(U13-OUT)") (class "Default")
      (node (ref "R4") (pin "2") (pinfunction "2_2") (pintype "passive"))
      (node (ref "U13") (pin "1") (pinfunction "OUT_1") (pintype "output"))
    )
    (net (code "41") (name "Net-(U13-VIN+)") (class "Default")
      (node (ref "R10") (pin "2") (pinfunction "2_2") (pintype "passive"))
      (node (ref "R9") (pin "2") (pinfunction "2_2") (pintype "passive"))
      (node (ref "U13") (pin "3") (pinfunction "VIN+_3") (pintype "input"))
    )
    (net (code "42") (name "RCLK") (class "Default")
      (node (ref "U1") (pin "13") (pinfunction "RCLK_13") (pintype "input"))
      (node (ref "U9") (pin "4") (pinfunction "Y_4") (pintype "output"))
    )
    (net (code "43") (name "RX") (class "Default")
      (node (ref "TP2") (pin "1") (pinfunction "P$1_1") (pintype "bidirectional"))
      (node (ref "U14") (pin "20") (pinfunction "PA7_20") (pintype "bidirectional"))
    )
    (net (code "44") (name "SCL") (class "Default")
      (node (ref "R11") (pin "1") (pinfunction "1_1") (pintype "passive"))
      (node (ref "TP5") (pin "1") (pinfunction "P$1_1") (pintype "bidirectional"))
      (node (ref "U12") (pin "7") (pinfunction "SCL_7") (pintype "bidirectional"))
      (node (ref "U14") (pin "10") (pinfunction "PC5_10") (pintype "bidirectional"))
    )
    (net (code "45") (name "SCL_EXT") (class "Default")
      (node (ref "ISP1") (pin "3") (pinfunction "SCK_3") (pintype "output"))
      (node (ref "U14") (pin "14") (pinfunction "PC1_14") (pintype "bidirectional"))
      (node (ref "U16") (pin "2") (pinfunction "A1_2") (pintype "bidirectional"))
    )
    (net (code "46") (name "SCL_EXT_HV") (class "Default")
      (node (ref "J5") (pin "4") (pinfunction "4_4") (pintype "passive"))
      (node (ref "U16") (pin "7") (pinfunction "B1_7") (pintype "bidirectional"))
    )
    (net (code "47") (name "SDA") (class "Default")
      (node (ref "R12") (pin "1") (pinfunction "1_1") (pintype "passive"))
      (node (ref "TP4") (pin "1") (pinfunction "P$1_1") (pintype "bidirectional"))
      (node (ref "U12") (pin "8") (pinfunction "SDA_8") (pintype "bidirectional"))
      (node (ref "U14") (pin "11") (pinfunction "PC4_11") (pintype "bidirectional"))
    )
    (net (code "48") (name "SDA_EXT") (class "Default")
      (node (ref "ISP1") (pin "4") (pinfunction "MOSI_4") (pintype "output"))
      (node (ref "U14") (pin "18") (pinfunction "PB1_18") (pintype "bidirectional"))
      (node (ref "U16") (pin "3") (pinfunction "A2_3") (pintype "bidirectional"))
    )
    (net (code "49") (name "SDA_EXT_HV") (class "Default")
      (node (ref "J5") (pin "3") (pinfunction "3_3") (pintype "passive"))
      (node (ref "U16") (pin "6") (pinfunction "B2_6") (pintype "bidirectional"))
    )
    (net (code "50") (name "THERM_SENSE") (class "Default")
      (node (ref "R15") (pin "2") (pinfunction "2_2") (pintype "passive"))
      (node (ref "RT1") (pin "2") (pinfunction "1_2") (pintype "passive"))
      (node (ref "U14") (pin "1") (pinfunction "PA6_1") (pintype "bidirectional"))
    )
    (net (code "51") (name "TX") (class "Default")
      (node (ref "TP1") (pin "1") (pinfunction "P$1_1") (pintype "bidirectional"))
      (node (ref "U14") (pin "19") (pinfunction "PB0_19") (pintype "bidirectional"))
    )
    (net (code "52") (name "URES") (class "Default")
      (node (ref "TP6") (pin "1") (pinfunction "P$1_1") (pintype "bidirectional"))
      (node (ref "U10") (pin "1") (pinfunction "A_1") (pintype "input"))
      (node (ref "U14") (pin "3") (pinfunction "PA4_3") (pintype "bidirectional"))
      (node (ref "U7") (pin "6") (pinfunction "~{CLR}_6") (pintype "output"))
    )
    (net (code "53") (name "VIN+") (class "Default")
      (node (ref "C1") (pin "1") (pinfunction "1_1") (pintype "passive"))
      (node (ref "C11") (pin "1") (pinfunction "1_1") (pintype "passive"))
      (node (ref "C14") (pin "1") (pinfunction "1_1") (pintype "passive"))
      (node (ref "J1") (pin "P2") (pinfunction "2_P2") (pintype "passive"))
      (node (ref "J2") (pin "P2") (pinfunction "2_P2") (pintype "passive"))
      (node (ref "J5") (pin "2") (pinfunction "2_2") (pintype "passive"))
      (node (ref "Q1") (pin "1") (pinfunction "G_1") (pintype "bidirectional"))
      (node (ref "U$1") (pin "4") (pinfunction "VIN_4") (pintype "bidirectional"))
      (node (ref "U16") (pin "8") (pinfunction "VB_8") (pintype "power_in"))
    )
    (net (code "54") (name "VIN-") (class "Default")
      (node (ref "J5") (pin "1") (pinfunction "1_1") (pintype "passive"))
      (node (ref "Q1") (pin "3") (pinfunction "D_3") (pintype "bidirectional"))
    )
    (net (code "55") (name "VREF") (class "Default")
      (node (ref "D1") (pin "1") (pinfunction "C_1") (pintype "power_in"))
      (node (ref "R14") (pin "1") (pinfunction "1_1") (pintype "passive"))
      (node (ref "RT1") (pin "1") (pinfunction "2_1") (pintype "passive"))
      (node (ref "U12") (pin "2") (pinfunction "VREF_2") (pintype "power_in"))
      (node (ref "U14") (pin "7") (pinfunction "PA0_7") (pintype "bidirectional"))
    )
    (net (code "56") (name "V_SET1") (class "Default")
      (node (ref "C15") (pin "1") (pinfunction "1_1") (pintype "passive"))
      (node (ref "R7") (pin "1") (pinfunction "1_1") (pintype "passive"))
      (node (ref "U12") (pin "3") (pinfunction "VOUT0_3") (pintype "output"))
    )
    (net (code "57") (name "V_SET2") (class "Default")
      (node (ref "C12") (pin "1") (pinfunction "1_1") (pintype "passive"))
      (node (ref "R9") (pin "1") (pinfunction "1_1") (pintype "passive"))
      (node (ref "U12") (pin "4") (pinfunction "VOUT1_4") (pintype "output"))
    )
    (net (code "58") (name "unconnected-(U$1-PG-Pad1)") (class "Default")
      (node (ref "U$1") (pin "1") (pinfunction "PG_1") (pintype "bidirectional"))
    )
    (net (code "59") (name "unconnected-(U1-~{RCO}-Pad9)") (class "Default")
      (node (ref "U1") (pin "9") (pinfunction "~{RCO}_9") (pintype "output"))
    )
    (net (code "60") (name "unconnected-(U6-~{Q}-Pad3)") (class "Default")
      (node (ref "U6") (pin "3") (pinfunction "~{Q}_3") (pintype "output"))
    )
    (net (code "61") (name "unconnected-(U7-~{Q}-Pad3)") (class "Default")
      (node (ref "U7") (pin "3") (pinfunction "~{Q}_3") (pintype "output"))
    )
    (net (code "62") (name "unconnected-(U8-~{Q}-Pad3)") (class "Default")
      (node (ref "U8") (pin "3") (pinfunction "~{Q}_3") (pintype "output"))
    )
    (net (code "63") (name "unconnected-(U12-~{LAT}-Pad6)") (class "Default")
      (node (ref "U12") (pin "6") (pinfunction "~{LAT}_6") (pintype "input"))
    )
    (net (code "64") (name "~{CLEAR}") (class "Default")
      (node (ref "U14") (pin "5") (pinfunction "PA2_5") (pintype "bidirectional"))
      (node (ref "U3") (pin "9") (pinfunction "~{CLR}_9") (pintype "input"))
    )
    (net (code "65") (name "~{COUNTRES}") (class "Default")
      (node (ref "U10") (pin "4") (pinfunction "Y_4") (pintype "output"))
      (node (ref "U9") (pin "1") (pinfunction "A_1") (pintype "input"))
    )
    (net (code "66") (name "~{F_IN}") (class "Default")
      (node (ref "U5") (pin "4") (pinfunction "Y_4") (pintype "bidirectional"))
      (node (ref "U7") (pin "1") (pinfunction "CLK_1") (pintype "output"))
    )
    (net (code "67") (name "~{INT}") (class "Default")
      (node (ref "TP3") (pin "1") (pinfunction "P$1_1") (pintype "bidirectional"))
      (node (ref "U14") (pin "13") (pinfunction "PC2_13") (pintype "bidirectional"))
      (node (ref "U8") (pin "5") (pinfunction "Q_5") (pintype "output"))
    )
    (net (code "68") (name "~{P=Q}") (class "Default")
      (node (ref "U10") (pin "2") (pinfunction "B_2") (pintype "input"))
      (node (ref "U17") (pin "2") (pinfunction "B_2") (pintype "input"))
      (node (ref "U2") (pin "19") (pinfunction "Y_19") (pintype "output"))
      (node (ref "U6") (pin "7") (pinfunction "~{PRE}_7") (pintype "output"))
    )
    (net (code "69") (name "~{RESET}") (class "Default")
      (node (ref "ISP1") (pin "5") (pinfunction "RST_5") (pintype "output"))
      (node (ref "R13") (pin "1") (pinfunction "1_1") (pintype "passive"))
      (node (ref "U14") (pin "12") (pinfunction "PC3_12") (pintype "bidirectional"))
    )
    (net (code "70") (name "~{SYNCRES}") (class "Default")
      (node (ref "U1") (pin "10") (pinfunction "~{CCLR}_10") (pintype "input"))
      (node (ref "U17") (pin "1") (pinfunction "A_1") (pintype "input"))
      (node (ref "U6") (pin "6") (pinfunction "~{CLR}_6") (pintype "output"))
      (node (ref "U7") (pin "5") (pinfunction "Q_5") (pintype "output"))
    )
  )
)
